# usblipocharger-own.net
KiCad netlist of a schematic drawn in EAGLE
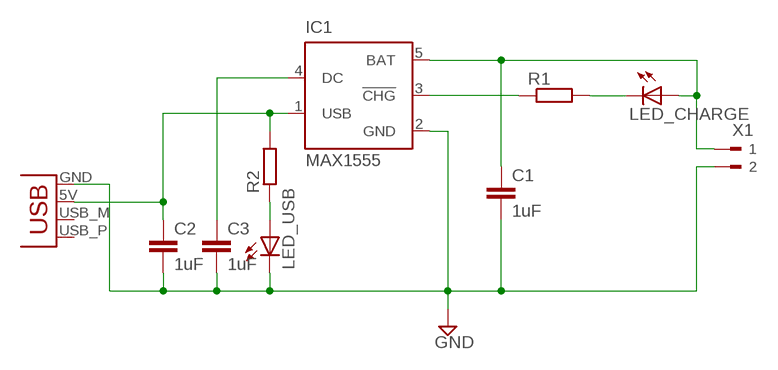
[diagram p0: schematic, sheet 1]

(export (version "E")
  (design (tool "Eeschema 10.0.6"))
  (components
    (comp (ref "C1")
      (value "1uF")
      (footprint "eagle-import:C0805")
      (libsource (lib "eagle-import") (part "C-EUC0805"))
    )
    (comp (ref "C2")
      (value "1uF")
      (footprint "eagle-import:C0805")
      (libsource (lib "eagle-import") (part "C-EUC0805"))
    )
    (comp (ref "C3")
      (value "1uF")
      (footprint "eagle-import:C0805")
      (libsource (lib "eagle-import") (part "C-EUC0805"))
    )
    (comp (ref "IC1")
      (value "MAX1555")
      (footprint "eagle-import:SOT23-5L")
      (libsource (lib "eagle-import") (part "MAX1555"))
    )
    (comp (ref "JP1")
      (value "USBPCB")
      (footprint "eagle-import:USB-A-PCB")
      (libsource (lib "eagle-import") (part "USBPCB"))
    )
    (comp (ref "LED_CHARGE")
      (value "LEDCHIP-LED0805")
      (footprint "eagle-import:CHIP-LED0805")
      (libsource (lib "eagle-import") (part "LEDCHIP-LED0805"))
    )
    (comp (ref "LED_USB")
      (value "LEDCHIP-LED0805")
      (footprint "eagle-import:CHIP-LED0805")
      (libsource (lib "eagle-import") (part "LEDCHIP-LED0805"))
    )
    (comp (ref "R1")
      (value "R-EU_R0805")
      (footprint "eagle-import:R0805")
      (libsource (lib "eagle-import") (part "R-EU_R0805"))
    )
    (comp (ref "R2")
      (value "R-EU_R0805")
      (footprint "eagle-import:R0805")
      (libsource (lib "eagle-import") (part "R-EU_R0805"))
    )
    (comp (ref "X1")
      (value "180-2")
      (footprint "eagle-import:180-2")
      (libsource (lib "eagle-import") (part "180-2"))
    )
  )
  (nets
    (net (code "1") (name "GND") (class "Default")
      (node (ref "C1") (pin "2") (pinfunction "2_2") (pintype "passive"))
      (node (ref "C2") (pin "2") (pinfunction "2_2") (pintype "passive"))
      (node (ref "C3") (pin "2") (pinfunction "2_2") (pintype "passive"))
      (node (ref "IC1") (pin "2") (pinfunction "GND_2") (pintype "power_in"))
      (node (ref "JP1") (pin "GND") (pinfunction "GND_GND") (pintype "bidirectional"))
      (node (ref "LED_USB") (pin "C") (pinfunction "C_C") (pintype "passive"))
      (node (ref "X1") (pin "2") (pinfunction "2_2") (pintype "passive"))
    )
    (net (code "2") (name "Net-(IC1-BAT)") (class "Default")
      (node (ref "C1") (pin "1") (pinfunction "1_1") (pintype "passive"))
      (node (ref "IC1") (pin "5") (pinfunction "BAT_5") (pintype "passive"))
      (node (ref "LED_CHARGE") (pin "A") (pinfunction "A_A") (pintype "passive"))
      (node (ref "X1") (pin "1") (pinfunction "1_1") (pintype "passive"))
    )
    (net (code "3") (name "Net-(IC1-DC)") (class "Default")
      (node (ref "C3") (pin "1") (pinfunction "1_1") (pintype "passive"))
      (node (ref "IC1") (pin "4") (pinfunction "DC_4") (pintype "input"))
    )
    (net (code "4") (name "Net-(IC1-USB)") (class "Default")
      (node (ref "C2") (pin "1") (pinfunction "1_1") (pintype "passive"))
      (node (ref "IC1") (pin "1") (pinfunction "USB_1") (pintype "input"))
      (node (ref "JP1") (pin "5V") (pinfunction "VBUS_5V") (pintype "bidirectional"))
      (node (ref "R2") (pin "2") (pinfunction "2_2") (pintype "passive"))
    )
    (net (code "5") (name "Net-(IC1-~{CHG})") (class "Default")
      (node (ref "IC1") (pin "3") (pinfunction "~{CHG}_3") (pintype "output"))
      (node (ref "R1") (pin "1") (pinfunction "1_1") (pintype "passive"))
    )
    (net (code "6") (name "Net-(LED_CHARGE-PadC)") (class "Default")
      (node (ref "LED_CHARGE") (pin "C") (pinfunction "C_C") (pintype "passive"))
      (node (ref "R1") (pin "2") (pinfunction "2_2") (pintype "passive"))
    )
    (net (code "7") (name "Net-(LED_USB-PadA)") (class "Default")
      (node (ref "LED_USB") (pin "A") (pinfunction "A_A") (pintype "passive"))
      (node (ref "R2") (pin "1") (pinfunction "1_1") (pintype "passive"))
    )
    (net (code "8") (name "unconnected-(JP1-D+-PadUSB_P)") (class "Default")
      (node (ref "JP1") (pin "USB_P") (pinfunction "D+_USB_P") (pintype "bidirectional"))
    )
    (net (code "9") (name "unconnected-(JP1-D--PadUSB_M)") (class "Default")
      (node (ref "JP1") (pin "USB_M") (pinfunction "D-_USB_M") (pintype "bidirectional"))
    )
  )
)
